# DRV8301_Motor.net
KiCad netlist of a schematic drawn in Altium Designer
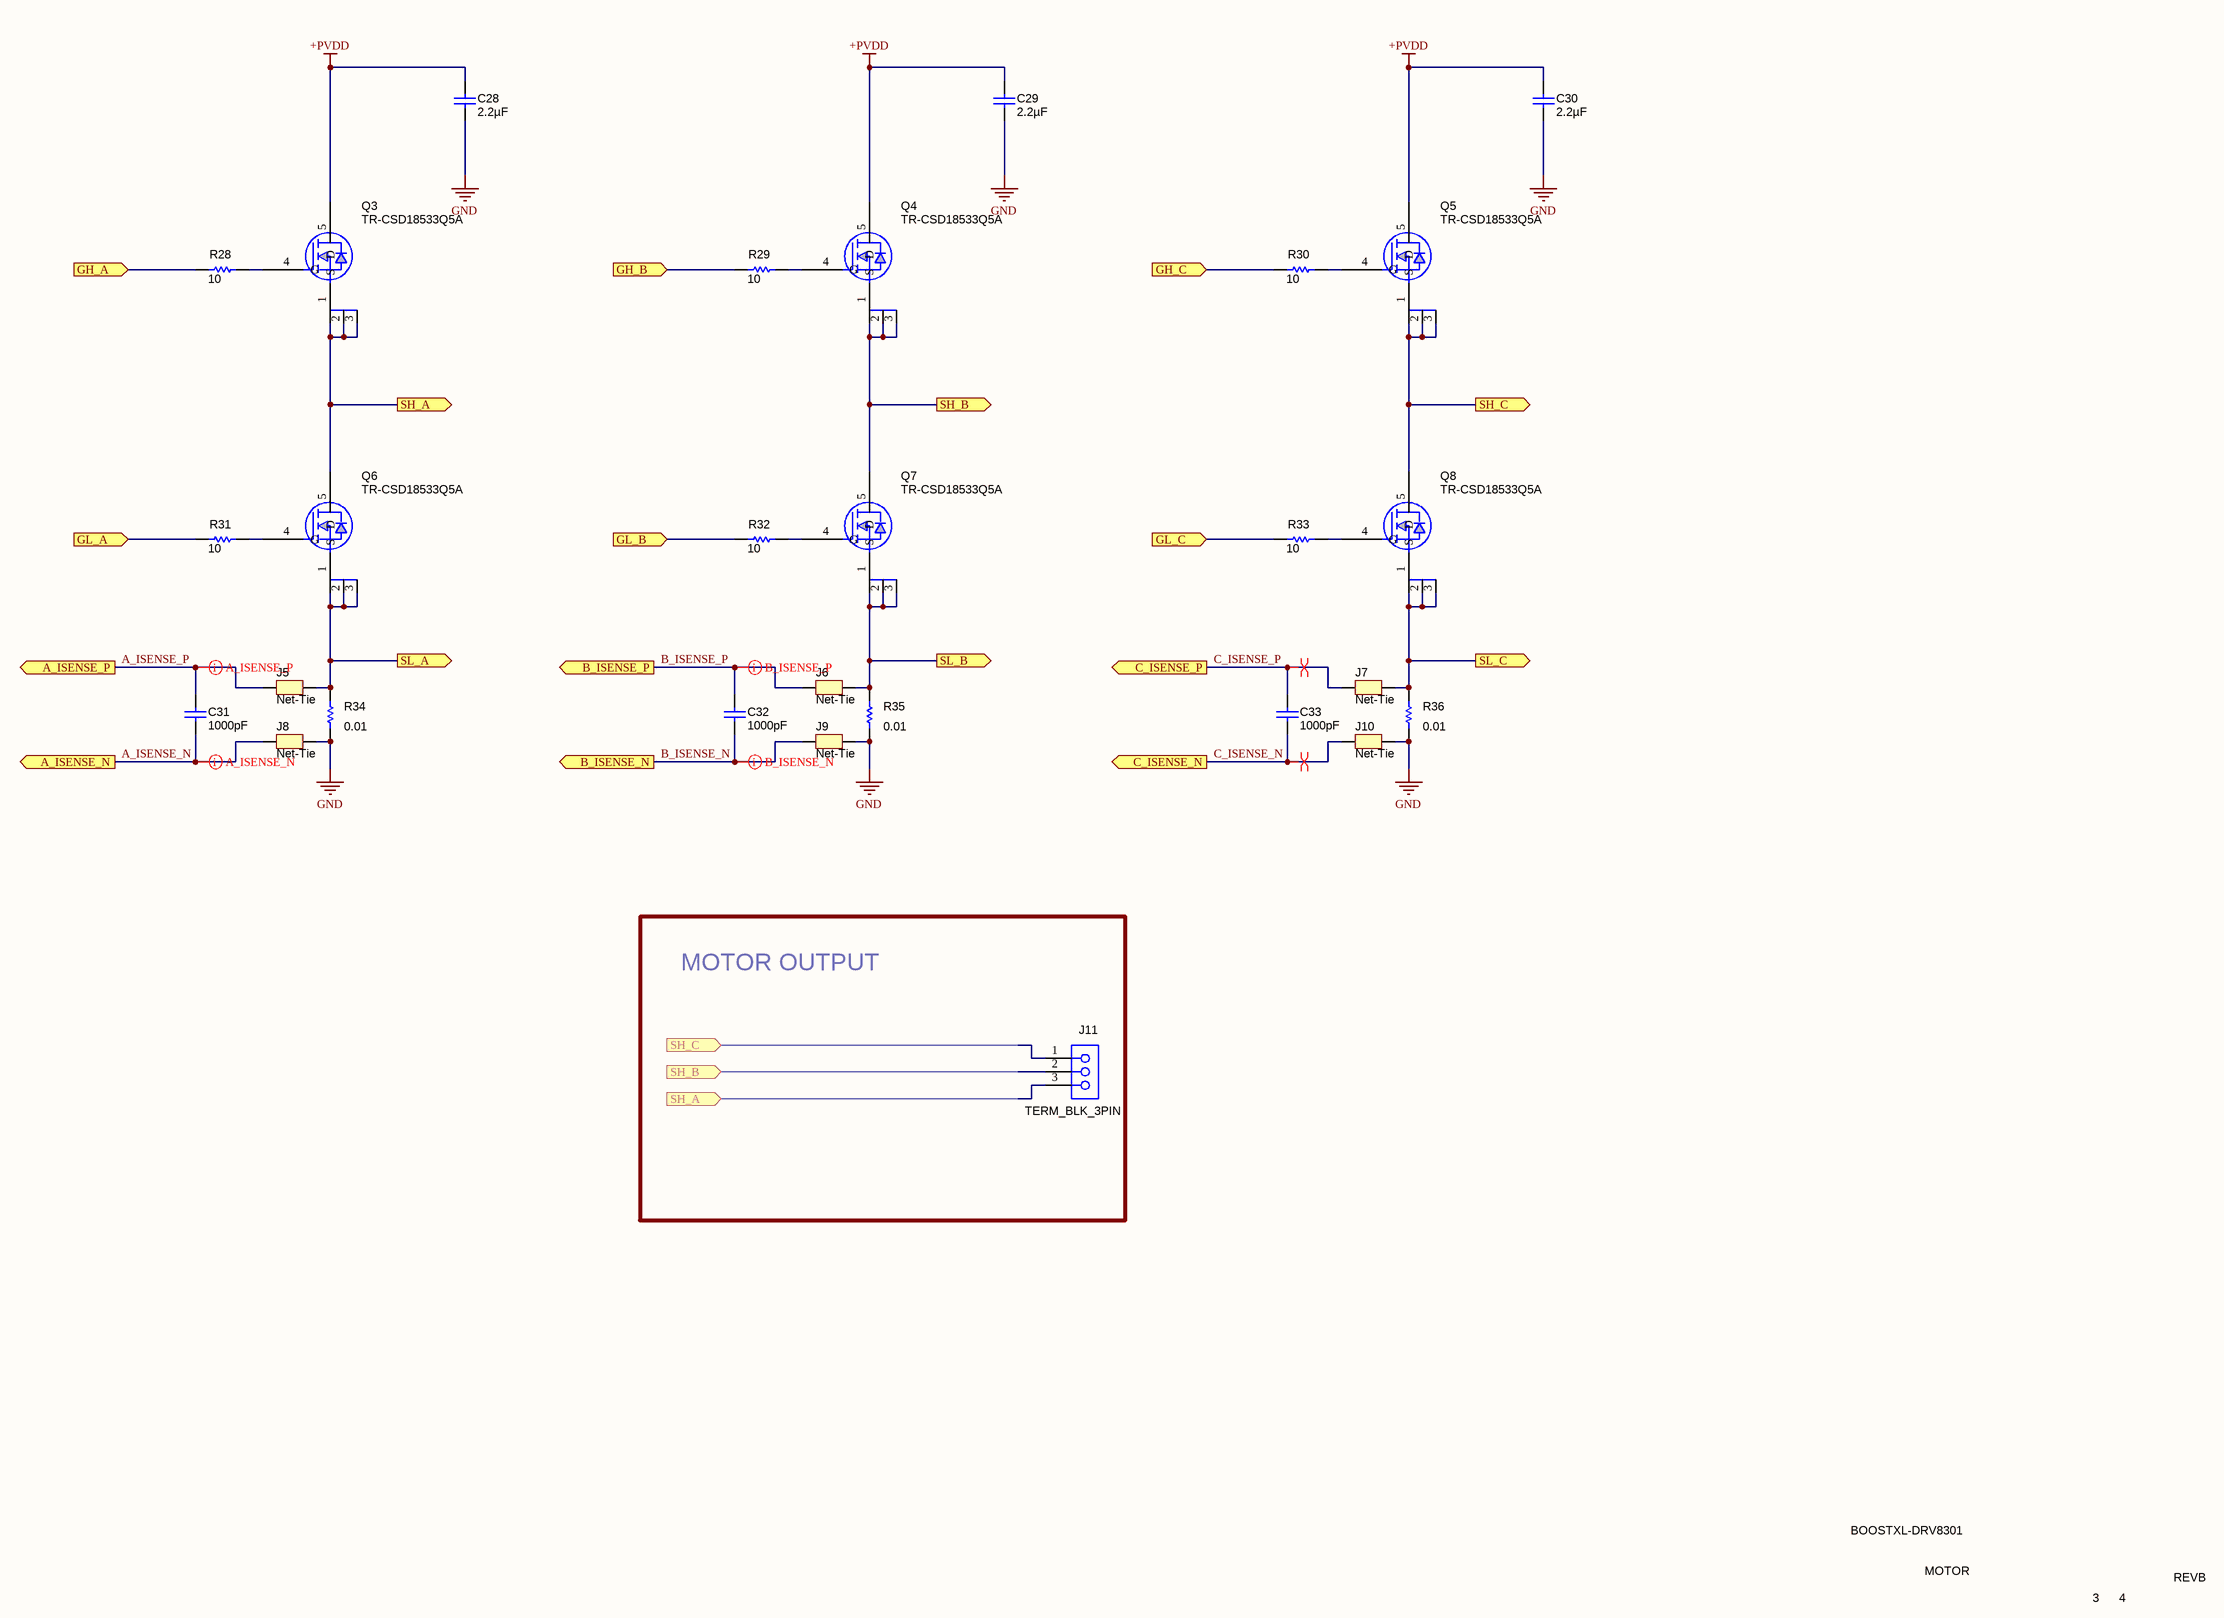
[diagram p0: DRV8301_Motor.SchDoc]

(export (version "E")
  (design (tool "Eeschema 10.0.6"))
  (components
    (comp (ref "C28")
      (value "GRM32ER72A225KA35L")
      (footprint "1210L")
      (description "CAP, CERM, 2.2uF, 100V, +/-10%, X7R, 1210")
      (fields
        (field (name "VALUEDISPLAYED") "2.2µF")
        (field (name "MANUFACTURER") "MuRata")
        (field (name "PUBLISHER") "Texas Instruments")
      )
      (libsource (lib "Capacitor_Ceramic") (part "GRM32ER72A225KA35L"))
    )
    (comp (ref "C29")
      (value "GRM32ER72A225KA35L")
      (footprint "1210L")
      (description "CAP, CERM, 2.2uF, 100V, +/-10%, X7R, 1210")
      (fields
        (field (name "VALUEDISPLAYED") "2.2µF")
        (field (name "MANUFACTURER") "MuRata")
        (field (name "PUBLISHER") "Texas Instruments")
      )
      (libsource (lib "Capacitor_Ceramic") (part "GRM32ER72A225KA35L"))
    )
    (comp (ref "C30")
      (value "GRM32ER72A225KA35L")
      (footprint "1210L")
      (description "CAP, CERM, 2.2uF, 100V, +/-10%, X7R, 1210")
      (fields
        (field (name "VALUEDISPLAYED") "2.2µF")
        (field (name "MANUFACTURER") "MuRata")
        (field (name "PUBLISHER") "Texas Instruments")
      )
      (libsource (lib "Capacitor_Ceramic") (part "GRM32ER72A225KA35L"))
    )
    (comp (ref "C31")
      (value "C0603C102J5GAC")
      (footprint "0603")
      (description "CAP, CERM, 1000pF, 50V, +/-5%, C0G/NP0, 0603")
      (fields
        (field (name "VALUEDISPLAYED") "1000pF")
        (field (name "MANUFACTURER") "Kemet")
        (field (name "PUBLISHER") "Texas Instruments")
      )
      (libsource (lib "Capacitor_Ceramic") (part "C0603C102J5GAC"))
    )
    (comp (ref "C32")
      (value "C0603C102J5GAC")
      (footprint "0603")
      (description "CAP, CERM, 1000pF, 50V, +/-5%, C0G/NP0, 0603")
      (fields
        (field (name "VALUEDISPLAYED") "1000pF")
        (field (name "MANUFACTURER") "Kemet")
        (field (name "PUBLISHER") "Texas Instruments")
      )
      (libsource (lib "Capacitor_Ceramic") (part "C0603C102J5GAC"))
    )
    (comp (ref "C33")
      (value "C0603C102J5GAC")
      (footprint "0603")
      (description "CAP, CERM, 1000pF, 50V, +/-5%, C0G/NP0, 0603")
      (fields
        (field (name "VALUEDISPLAYED") "1000pF")
        (field (name "MANUFACTURER") "Kemet")
        (field (name "PUBLISHER") "Texas Instruments")
      )
      (libsource (lib "Capacitor_Ceramic") (part "C0603C102J5GAC"))
    )
    (comp (ref "J5")
      (value "Net-Tie")
      (footprint "Net-Tie_10mil")
      (description "Single point connection between nets.")
      (fields (field (name "SYMBOLCREATOR") "codlsc") (field (name "PUBLISHER") "Texas Instruments"))
      (libsource (lib "MiscParts") (part "Net-Tie"))
    )
    (comp (ref "J6")
      (value "Net-Tie")
      (footprint "Net-Tie_10mil")
      (description "Single point connection between nets.")
      (fields (field (name "SYMBOLCREATOR") "codlsc") (field (name "PUBLISHER") "Texas Instruments"))
      (libsource (lib "MiscParts") (part "Net-Tie"))
    )
    (comp (ref "J7")
      (value "Net-Tie")
      (footprint "Net-Tie_10mil")
      (description "Single point connection between nets.")
      (fields (field (name "SYMBOLCREATOR") "codlsc") (field (name "PUBLISHER") "Texas Instruments"))
      (libsource (lib "MiscParts") (part "Net-Tie"))
    )
    (comp (ref "J8")
      (value "Net-Tie")
      (footprint "Net-Tie_10mil")
      (description "Single point connection between nets.")
      (fields (field (name "SYMBOLCREATOR") "codlsc") (field (name "PUBLISHER") "Texas Instruments"))
      (libsource (lib "MiscParts") (part "Net-Tie"))
    )
    (comp (ref "J9")
      (value "Net-Tie")
      (footprint "Net-Tie_10mil")
      (description "Single point connection between nets.")
      (fields (field (name "SYMBOLCREATOR") "codlsc") (field (name "PUBLISHER") "Texas Instruments"))
      (libsource (lib "MiscParts") (part "Net-Tie"))
    )
    (comp (ref "J10")
      (value "Net-Tie")
      (footprint "Net-Tie_10mil")
      (description "Single point connection between nets.")
      (fields (field (name "SYMBOLCREATOR") "codlsc") (field (name "PUBLISHER") "Texas Instruments"))
      (libsource (lib "MiscParts") (part "Net-Tie"))
    )
    (comp (ref "J11")
      (value "TERM_BLK_3PIN")
      (footprint "CONN_ED120_3DS")
      (description "TERMINAL BLOCK 5.08MM VERT 3POS")
      (fields
        (field (name "PARTNUMBER") "OSTTA034163")
        (field (name "MANUFACTURER") "On-Shore Technology")
        (field (name "SYMBOLCREATOR") "a0412235")
        (field (name "PUBLISHER") "Texas Instruments")
      )
      (libsource (lib "Connectors") (part "ED120/3DS"))
    )
    (comp (ref "Q3")
      (value "TR-CSD18533Q5A")
      (footprint "QFN5X6MM")
      (description "MOSFET, N-Chan, 60V, 18A, 6.1 mOhm")
      (fields (field (name "MANUFACTURER") "TI") (field (name "PARTNUMBER") "CSD18533Q5A"))
      (libsource (lib "PADSlegacy_Active") (part "TR-CSD18533Q5A"))
    )
    (comp (ref "Q4")
      (value "TR-CSD18533Q5A")
      (footprint "QFN5X6MM")
      (description "MOSFET, N-Chan, 60V, 18A, 6.1 mOhm")
      (fields (field (name "MANUFACTURER") "TI") (field (name "PARTNUMBER") "CSD18533Q5A"))
      (libsource (lib "PADSlegacy_Active") (part "TR-CSD18533Q5A"))
    )
    (comp (ref "Q5")
      (value "TR-CSD18533Q5A")
      (footprint "QFN5X6MM")
      (description "MOSFET, N-Chan, 60V, 18A, 6.1 mOhm")
      (fields (field (name "MANUFACTURER") "TI") (field (name "PARTNUMBER") "CSD18533Q5A"))
      (libsource (lib "PADSlegacy_Active") (part "TR-CSD18533Q5A"))
    )
    (comp (ref "Q6")
      (value "TR-CSD18533Q5A")
      (footprint "QFN5X6MM")
      (description "MOSFET, N-Chan, 60V, 18A, 6.1 mOhm")
      (fields (field (name "MANUFACTURER") "TI") (field (name "PARTNUMBER") "CSD18533Q5A"))
      (libsource (lib "PADSlegacy_Active") (part "TR-CSD18533Q5A"))
    )
    (comp (ref "Q7")
      (value "TR-CSD18533Q5A")
      (footprint "QFN5X6MM")
      (description "MOSFET, N-Chan, 60V, 18A, 6.1 mOhm")
      (fields (field (name "MANUFACTURER") "TI") (field (name "PARTNUMBER") "CSD18533Q5A"))
      (libsource (lib "PADSlegacy_Active") (part "TR-CSD18533Q5A"))
    )
    (comp (ref "Q8")
      (value "TR-CSD18533Q5A")
      (footprint "QFN5X6MM")
      (description "MOSFET, N-Chan, 60V, 18A, 6.1 mOhm")
      (fields (field (name "MANUFACTURER") "TI") (field (name "PARTNUMBER") "CSD18533Q5A"))
      (libsource (lib "PADSlegacy_Active") (part "TR-CSD18533Q5A"))
    )
    (comp (ref "R28")
      (value "10")
      (footprint "0603L")
      (description "RES, 10 ohm, 5%, 0.1W, 0603")
      (fields
        (field (name "PARTNUMBER") "CRCW060310R0JNEA")
        (field (name "MANUFACTURER") "Vishay-Dale")
        (field (name "PUBLISHER") "Texas Instruments")
      )
      (libsource (lib "Resistor_0603") (part "CRCW060310R0JNEA"))
    )
    (comp (ref "R29")
      (value "10")
      (footprint "0603L")
      (description "RES, 10 ohm, 5%, 0.1W, 0603")
      (fields
        (field (name "PARTNUMBER") "CRCW060310R0JNEA")
        (field (name "MANUFACTURER") "Vishay-Dale")
        (field (name "PUBLISHER") "Texas Instruments")
      )
      (libsource (lib "Resistor_0603") (part "CRCW060310R0JNEA"))
    )
    (comp (ref "R30")
      (value "10")
      (footprint "0603L")
      (description "RES, 10 ohm, 5%, 0.1W, 0603")
      (fields
        (field (name "PARTNUMBER") "CRCW060310R0JNEA")
        (field (name "MANUFACTURER") "Vishay-Dale")
        (field (name "PUBLISHER") "Texas Instruments")
      )
      (libsource (lib "Resistor_0603") (part "CRCW060310R0JNEA"))
    )
    (comp (ref "R31")
      (value "10")
      (footprint "0603L")
      (description "RES, 10 ohm, 5%, 0.1W, 0603")
      (fields
        (field (name "PARTNUMBER") "CRCW060310R0JNEA")
        (field (name "MANUFACTURER") "Vishay-Dale")
        (field (name "PUBLISHER") "Texas Instruments")
      )
      (libsource (lib "Resistor_0603") (part "CRCW060310R0JNEA"))
    )
    (comp (ref "R32")
      (value "10")
      (footprint "0603L")
      (description "RES, 10 ohm, 5%, 0.1W, 0603")
      (fields
        (field (name "PARTNUMBER") "CRCW060310R0JNEA")
        (field (name "MANUFACTURER") "Vishay-Dale")
        (field (name "PUBLISHER") "Texas Instruments")
      )
      (libsource (lib "Resistor_0603") (part "CRCW060310R0JNEA"))
    )
    (comp (ref "R33")
      (value "10")
      (footprint "0603L")
      (description "RES, 10 ohm, 5%, 0.1W, 0603")
      (fields
        (field (name "PARTNUMBER") "CRCW060310R0JNEA")
        (field (name "MANUFACTURER") "Vishay-Dale")
        (field (name "PUBLISHER") "Texas Instruments")
      )
      (libsource (lib "Resistor_0603") (part "CRCW060310R0JNEA"))
    )
    (comp (ref "R34")
      (value "0.01")
      (footprint "2512M")
      (description "RES, 0.01 ohm, 1%, 3W, 2512")
      (fields
        (field (name "PARTNUMBER") "CRA2512-FZ-R010ELF")
        (field (name "MANUFACTURER") "Bourns")
        (field (name "PUBLISHER") "Texas Instruments")
      )
      (libsource (lib "Resistor_OtherSMT") (part "CRA2512-FZ-R010ELF"))
    )
    (comp (ref "R35")
      (value "0.01")
      (footprint "2512M")
      (description "RES, 0.01 ohm, 1%, 3W, 2512")
      (fields
        (field (name "PARTNUMBER") "CRA2512-FZ-R010ELF")
        (field (name "MANUFACTURER") "Bourns")
        (field (name "PUBLISHER") "Texas Instruments")
      )
      (libsource (lib "Resistor_OtherSMT") (part "CRA2512-FZ-R010ELF"))
    )
    (comp (ref "R36")
      (value "0.01")
      (footprint "2512M")
      (description "RES, 0.01 ohm, 1%, 3W, 2512")
      (fields
        (field (name "PARTNUMBER") "CRA2512-FZ-R010ELF")
        (field (name "MANUFACTURER") "Bourns")
        (field (name "PUBLISHER") "Texas Instruments")
      )
      (libsource (lib "Resistor_OtherSMT") (part "CRA2512-FZ-R010ELF"))
    )
  )
  (nets
    (net (code "1") (name "+PVDD") (class "Default")
      (node (ref "C28") (pin "1") (pinfunction "1_1") (pintype "passive"))
      (node (ref "C29") (pin "1") (pinfunction "1_1") (pintype "passive"))
      (node (ref "C30") (pin "1") (pinfunction "1_1") (pintype "passive"))
      (node (ref "Q3") (pin "5") (pinfunction "D_5") (pintype "passive"))
      (node (ref "Q4") (pin "5") (pinfunction "D_5") (pintype "passive"))
      (node (ref "Q5") (pin "5") (pinfunction "D_5") (pintype "passive"))
    )
    (net (code "2") (name "/A_ISENSE_N") (class "Default")
      (node (ref "C31") (pin "2") (pinfunction "2_2") (pintype "passive"))
      (node (ref "J8") (pin "2") (pinfunction "2_2") (pintype "passive"))
    )
    (net (code "3") (name "/A_ISENSE_P") (class "Default")
      (node (ref "C31") (pin "1") (pinfunction "1_1") (pintype "passive"))
      (node (ref "J5") (pin "2") (pinfunction "2_2") (pintype "passive"))
    )
    (net (code "4") (name "/B_ISENSE_N") (class "Default")
      (node (ref "C32") (pin "2") (pinfunction "2_2") (pintype "passive"))
      (node (ref "J9") (pin "2") (pinfunction "2_2") (pintype "passive"))
    )
    (net (code "5") (name "/B_ISENSE_P") (class "Default")
      (node (ref "C32") (pin "1") (pinfunction "1_1") (pintype "passive"))
      (node (ref "J6") (pin "2") (pinfunction "2_2") (pintype "passive"))
    )
    (net (code "6") (name "/C_ISENSE_N") (class "Default")
      (node (ref "C33") (pin "2") (pinfunction "2_2") (pintype "passive"))
      (node (ref "J10") (pin "2") (pinfunction "2_2") (pintype "passive"))
    )
    (net (code "7") (name "/C_ISENSE_P") (class "Default")
      (node (ref "C33") (pin "1") (pinfunction "1_1") (pintype "passive"))
      (node (ref "J7") (pin "2") (pinfunction "2_2") (pintype "passive"))
    )
    (net (code "8") (name "/GH_A") (class "Default")
      (node (ref "R28") (pin "1") (pinfunction "1_1") (pintype "passive"))
    )
    (net (code "9") (name "/GH_B") (class "Default")
      (node (ref "R29") (pin "1") (pinfunction "1_1") (pintype "passive"))
    )
    (net (code "10") (name "/GH_C") (class "Default")
      (node (ref "R30") (pin "1") (pinfunction "1_1") (pintype "passive"))
    )
    (net (code "11") (name "/GL_A") (class "Default")
      (node (ref "R31") (pin "1") (pinfunction "1_1") (pintype "passive"))
    )
    (net (code "12") (name "/GL_B") (class "Default")
      (node (ref "R32") (pin "1") (pinfunction "1_1") (pintype "passive"))
    )
    (net (code "13") (name "/GL_C") (class "Default")
      (node (ref "R33") (pin "1") (pinfunction "1_1") (pintype "passive"))
    )
    (net (code "14") (name "/SH_A") (class "Default")
      (node (ref "J11") (pin "3") (pinfunction "3_3") (pintype "passive"))
      (node (ref "Q3") (pin "1") (pinfunction "S_1") (pintype "passive"))
      (node (ref "Q3") (pin "2") (pintype "passive"))
      (node (ref "Q3") (pin "3") (pintype "passive"))
      (node (ref "Q6") (pin "5") (pinfunction "D_5") (pintype "passive"))
    )
    (net (code "15") (name "/SH_B") (class "Default")
      (node (ref "J11") (pin "2") (pinfunction "2_2") (pintype "passive"))
      (node (ref "Q4") (pin "1") (pinfunction "S_1") (pintype "passive"))
      (node (ref "Q4") (pin "2") (pintype "passive"))
      (node (ref "Q4") (pin "3") (pintype "passive"))
      (node (ref "Q7") (pin "5") (pinfunction "D_5") (pintype "passive"))
    )
    (net (code "16") (name "/SH_C") (class "Default")
      (node (ref "J11") (pin "1") (pinfunction "1_1") (pintype "passive"))
      (node (ref "Q5") (pin "1") (pinfunction "S_1") (pintype "passive"))
      (node (ref "Q5") (pin "2") (pintype "passive"))
      (node (ref "Q5") (pin "3") (pintype "passive"))
      (node (ref "Q8") (pin "5") (pinfunction "D_5") (pintype "passive"))
    )
    (net (code "17") (name "/SL_A") (class "Default")
      (node (ref "J5") (pin "1") (pinfunction "1_1") (pintype "passive"))
      (node (ref "Q6") (pin "1") (pinfunction "S_1") (pintype "passive"))
      (node (ref "Q6") (pin "2") (pintype "passive"))
      (node (ref "Q6") (pin "3") (pintype "passive"))
      (node (ref "R34") (pin "2") (pinfunction "2_2") (pintype "passive"))
    )
    (net (code "18") (name "/SL_B") (class "Default")
      (node (ref "J6") (pin "1") (pinfunction "1_1") (pintype "passive"))
      (node (ref "Q7") (pin "1") (pinfunction "S_1") (pintype "passive"))
      (node (ref "Q7") (pin "2") (pintype "passive"))
      (node (ref "Q7") (pin "3") (pintype "passive"))
      (node (ref "R35") (pin "2") (pinfunction "2_2") (pintype "passive"))
    )
    (net (code "19") (name "/SL_C") (class "Default")
      (node (ref "J7") (pin "1") (pinfunction "1_1") (pintype "passive"))
      (node (ref "Q8") (pin "1") (pinfunction "S_1") (pintype "passive"))
      (node (ref "Q8") (pin "2") (pintype "passive"))
      (node (ref "Q8") (pin "3") (pintype "passive"))
      (node (ref "R36") (pin "2") (pinfunction "2_2") (pintype "passive"))
    )
    (net (code "20") (name "GND") (class "Default")
      (node (ref "C28") (pin "2") (pinfunction "2_2") (pintype "passive"))
      (node (ref "C29") (pin "2") (pinfunction "2_2") (pintype "passive"))
      (node (ref "C30") (pin "2") (pinfunction "2_2") (pintype "passive"))
      (node (ref "J10") (pin "1") (pinfunction "1_1") (pintype "passive"))
      (node (ref "J8") (pin "1") (pinfunction "1_1") (pintype "passive"))
      (node (ref "J9") (pin "1") (pinfunction "1_1") (pintype "passive"))
      (node (ref "R34") (pin "1") (pinfunction "1_1") (pintype "passive"))
      (node (ref "R35") (pin "1") (pinfunction "1_1") (pintype "passive"))
      (node (ref "R36") (pin "1") (pinfunction "1_1") (pintype "passive"))
    )
    (net (code "21") (name "Net-(Q3-G)") (class "Default")
      (node (ref "Q3") (pin "4") (pinfunction "G_4") (pintype "passive"))
      (node (ref "R28") (pin "2") (pinfunction "2_2") (pintype "passive"))
    )
    (net (code "22") (name "Net-(Q4-G)") (class "Default")
      (node (ref "Q4") (pin "4") (pinfunction "G_4") (pintype "passive"))
      (node (ref "R29") (pin "2") (pinfunction "2_2") (pintype "passive"))
    )
    (net (code "23") (name "Net-(Q5-G)") (class "Default")
      (node (ref "Q5") (pin "4") (pinfunction "G_4") (pintype "passive"))
      (node (ref "R30") (pin "2") (pinfunction "2_2") (pintype "passive"))
    )
    (net (code "24") (name "Net-(Q6-G)") (class "Default")
      (node (ref "Q6") (pin "4") (pinfunction "G_4") (pintype "passive"))
      (node (ref "R31") (pin "2") (pinfunction "2_2") (pintype "passive"))
    )
    (net (code "25") (name "Net-(Q7-G)") (class "Default")
      (node (ref "Q7") (pin "4") (pinfunction "G_4") (pintype "passive"))
      (node (ref "R32") (pin "2") (pinfunction "2_2") (pintype "passive"))
    )
    (net (code "26") (name "Net-(Q8-G)") (class "Default")
      (node (ref "Q8") (pin "4") (pinfunction "G_4") (pintype "passive"))
      (node (ref "R33") (pin "2") (pinfunction "2_2") (pintype "passive"))
    )
  )
)
